# schematic.net
KiCad netlist of a schematic drawn in Altium Designer
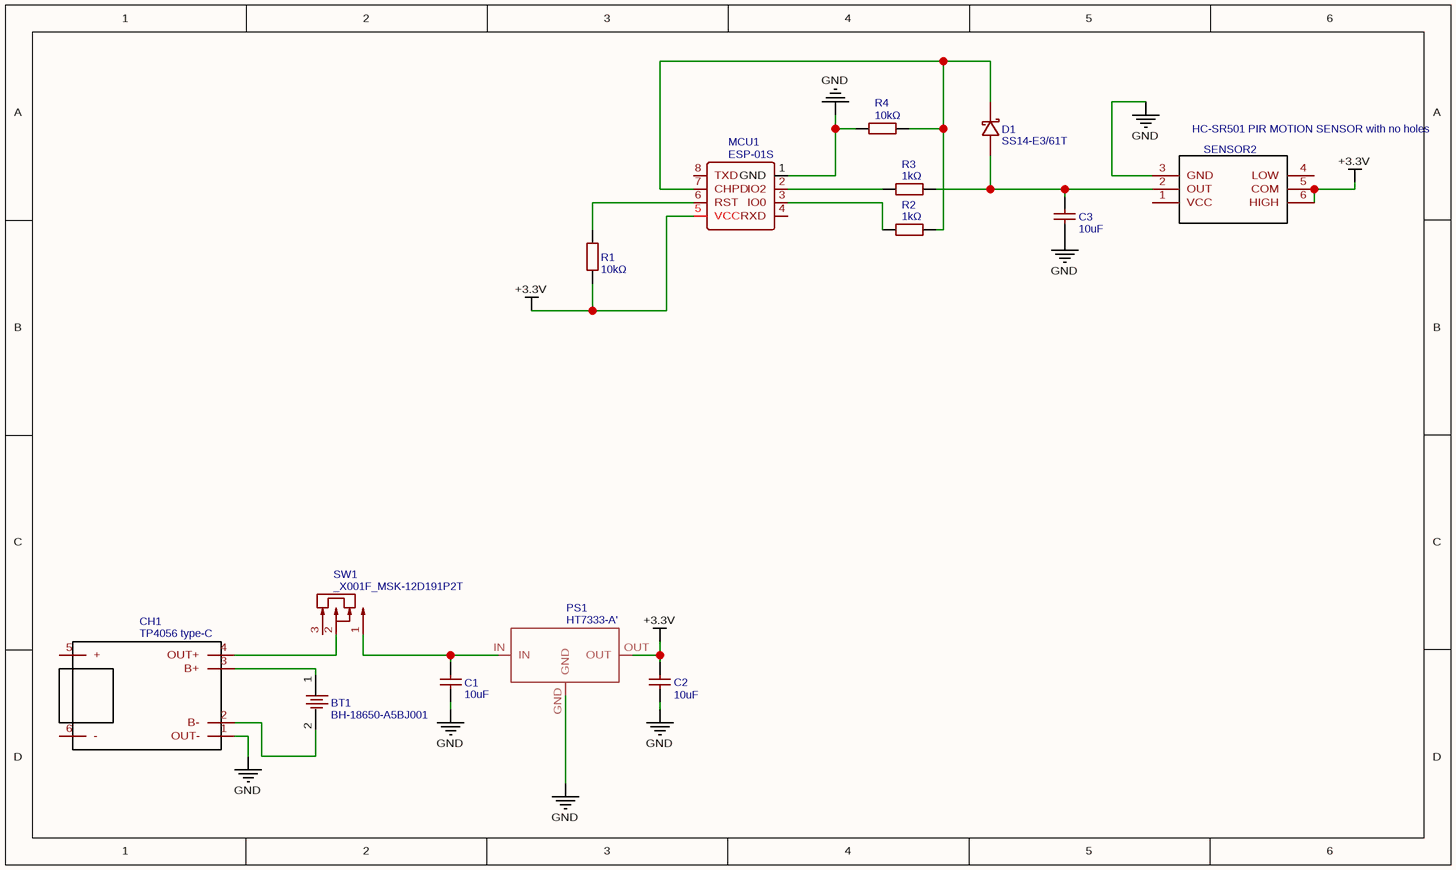
[diagram p0: schematic.schdoc]

(export (version "E")
  (design (tool "Eeschema 10.0.6"))
  (components
    (comp (ref "BT1")
      (value "BH-18650-A5BJ001")
      (fields (field (name "MANUFACTURER") "MYOUNG(美阳)") (field (name "CONTRIBUTOR") "lcsc"))
      (libsource (lib "altium-import") (part "root_3_BH-18650-A5BJ001_"))
    )
    (comp (ref "C1")
      (value "10uF")
      (fields
        (field (name "MANUFACTURER PART") "CL21A106KOQNNNE")
        (field (name "MANUFACTURER") "SAMSUNG(三星)")
      )
      (libsource (lib "altium-import") (part "root_1_10uF_"))
    )
    (comp (ref "C2")
      (value "10uF")
      (fields
        (field (name "MANUFACTURER PART") "CL21A106KOQNNNE")
        (field (name "MANUFACTURER") "SAMSUNG(三星)")
      )
      (libsource (lib "altium-import") (part "root_3_10uF_"))
    )
    (comp (ref "C3")
      (value "10uF")
      (fields
        (field (name "MANUFACTURER PART") "CL21A106KOQNNNE")
        (field (name "MANUFACTURER") "SAMSUNG(三星)")
      )
      (libsource (lib "altium-import") (part "root_3_10uF_"))
    )
    (comp (ref "CH1")
      (value "TP4056 type-C")
      (fields (field (name "CONTRIBUTOR") "red2211"))
      (libsource (lib "altium-import") (part "root_1_TP4056 type-C_"))
    )
    (comp (ref "D1")
      (value "SS14-E3/61T")
      (fields (field (name "MANUFACTURER") "VISHAY(威世)"))
      (libsource (lib "altium-import") (part "root_3_SS14-E3/61T_"))
    )
    (comp (ref "MCU1")
      (value "ESP-01S")
      (fields (field (name "MANUFACTURER") "Ai-Thinker"))
      (libsource (lib "altium-import") (part "root_3_ESP-01S_"))
    )
    (comp (ref "PS1")
      (value "HT7333-A'")
      (fields (field (name "CONTRIBUTOR") "userweb"))
      (libsource (lib "altium-import") (part "root_0_HT7333-A'_"))
    )
    (comp (ref "R1")
      (value "10kΩ")
      (fields
        (field (name "MANUFACTURER") "UNI-ROYAL(厚声)")
        (field (name "MANUFACTURER PART") "1206W4F1002T5E")
      )
      (libsource (lib "altium-import") (part "root_1_10kΩ_"))
    )
    (comp (ref "R2")
      (value "1kΩ")
      (fields
        (field (name "MANUFACTURER") "UNI-ROYAL(厚声)")
        (field (name "MANUFACTURER PART") "1206W4F1001T5E")
      )
      (libsource (lib "altium-import") (part "root_0_1kΩ_"))
    )
    (comp (ref "R3")
      (value "1kΩ")
      (fields
        (field (name "MANUFACTURER") "UNI-ROYAL(厚声)")
        (field (name "MANUFACTURER PART") "1206W4F1001T5E")
      )
      (libsource (lib "altium-import") (part "root_0_1kΩ_"))
    )
    (comp (ref "R4")
      (value "10kΩ")
      (fields
        (field (name "MANUFACTURER") "UNI-ROYAL(厚声)")
        (field (name "MANUFACTURER PART") "1206W4F1002T5E")
      )
      (libsource (lib "altium-import") (part "root_2_10kΩ_"))
    )
    (comp (ref "SENSOR2")
      (value "HC-SR501 PIR MOTION SENSOR with no holes")
      (fields (field (name "CONTRIBUTOR") "aryadpram"))
      (libsource (lib "altium-import") (part "root_0_HC-SR501 PIR MOTION SENSOR with no holes_"))
    )
    (comp (ref "SW1")
      (value "_X001F_MSK-12D191P2T")
      (fields (field (name "MANUFACTURER PART") "_x001F_MSK-12D191P2T") (field (name "CONTRIBUTOR") "lcsc"))
      (libsource (lib "altium-import") (part "root_2__X001F_MSK-12D191P2T_"))
    )
  )
  (nets
    (net (code "1") (name "+3.3V") (class "Default")
      (node (ref "C2") (pin "1") (pinfunction "1_1") (pintype "passive"))
      (node (ref "MCU1") (pin "5") (pinfunction "VCC_5") (pintype "passive"))
      (node (ref "PS1") (pin "OUT") (pinfunction "OUT_OUT") (pintype "passive"))
      (node (ref "R1") (pin "1") (pinfunction "1_1") (pintype "passive"))
      (node (ref "SENSOR2") (pin "5") (pinfunction "COM_5") (pintype "passive"))
      (node (ref "SENSOR2") (pin "6") (pinfunction "HIGH_6") (pintype "passive"))
    )
    (net (code "2") (name "GND") (class "Default")
      (node (ref "C1") (pin "1") (pinfunction "1_1") (pintype "passive"))
      (node (ref "C2") (pin "2") (pinfunction "2_2") (pintype "passive"))
      (node (ref "C3") (pin "2") (pinfunction "2_2") (pintype "passive"))
      (node (ref "CH1") (pin "1") (pinfunction "OUT-_1") (pintype "passive"))
      (node (ref "MCU1") (pin "1") (pinfunction "GND_1") (pintype "passive"))
      (node (ref "PS1") (pin "GND") (pinfunction "GND_GND") (pintype "passive"))
      (node (ref "R4") (pin "2") (pinfunction "2_2") (pintype "passive"))
      (node (ref "SENSOR2") (pin "3") (pinfunction "GND_3") (pintype "passive"))
    )
    (net (code "3") (name "Net-(C1-Pad2)") (class "Default")
      (node (ref "C1") (pin "2") (pinfunction "2_2") (pintype "passive"))
      (node (ref "PS1") (pin "IN") (pinfunction "IN_IN") (pintype "passive"))
      (node (ref "SW1") (pin "1") (pinfunction "1_1") (pintype "passive"))
    )
    (net (code "4") (name "Net-(CH1-B+)") (class "Default")
      (node (ref "BT1") (pin "1") (pinfunction "1_1") (pintype "passive"))
      (node (ref "CH1") (pin "3") (pinfunction "B+_3") (pintype "passive"))
    )
    (net (code "5") (name "Net-(CH1-B-)") (class "Default")
      (node (ref "BT1") (pin "2") (pinfunction "2_2") (pintype "passive"))
      (node (ref "CH1") (pin "2") (pinfunction "B-_2") (pintype "passive"))
    )
    (net (code "6") (name "Net-(CH1-OUT+)") (class "Default")
      (node (ref "CH1") (pin "4") (pinfunction "OUT+_4") (pintype "passive"))
      (node (ref "SW1") (pin "2") (pinfunction "2_2") (pintype "passive"))
    )
    (net (code "7") (name "Net-(D1-A)") (class "Default")
      (node (ref "C3") (pin "1") (pinfunction "1_1") (pintype "passive"))
      (node (ref "D1") (pin "2") (pinfunction "A_2") (pintype "passive"))
      (node (ref "R3") (pin "2") (pinfunction "2_2") (pintype "passive"))
      (node (ref "SENSOR2") (pin "2") (pinfunction "OUT_2") (pintype "passive"))
    )
    (net (code "8") (name "Net-(D1-K)") (class "Default")
      (node (ref "D1") (pin "1") (pinfunction "K_1") (pintype "passive"))
      (node (ref "MCU1") (pin "7") (pinfunction "CHPD_7") (pintype "passive"))
      (node (ref "R2") (pin "2") (pinfunction "2_2") (pintype "passive"))
      (node (ref "R4") (pin "1") (pinfunction "1_1") (pintype "passive"))
    )
    (net (code "9") (name "Net-(MCU1-IO0)") (class "Default")
      (node (ref "MCU1") (pin "3") (pinfunction "IO0_3") (pintype "passive"))
      (node (ref "R2") (pin "1") (pinfunction "1_1") (pintype "passive"))
    )
    (net (code "10") (name "Net-(MCU1-IO2)") (class "Default")
      (node (ref "MCU1") (pin "2") (pinfunction "IO2_2") (pintype "passive"))
      (node (ref "R3") (pin "1") (pinfunction "1_1") (pintype "passive"))
    )
    (net (code "11") (name "Net-(MCU1-RST)") (class "Default")
      (node (ref "MCU1") (pin "6") (pinfunction "RST_6") (pintype "passive"))
      (node (ref "R1") (pin "2") (pinfunction "2_2") (pintype "passive"))
    )
    (net (code "12") (name "unconnected-(CH1-+-Pad5)") (class "Default")
      (node (ref "CH1") (pin "5") (pinfunction "+_5") (pintype "passive"))
    )
    (net (code "13") (name "unconnected-(CH1---Pad6)") (class "Default")
      (node (ref "CH1") (pin "6") (pinfunction "-_6") (pintype "passive"))
    )
    (net (code "14") (name "unconnected-(MCU1-RXD-Pad4)") (class "Default")
      (node (ref "MCU1") (pin "4") (pinfunction "RXD_4") (pintype "passive"))
    )
    (net (code "15") (name "unconnected-(MCU1-TXD-Pad8)") (class "Default")
      (node (ref "MCU1") (pin "8") (pinfunction "TXD_8") (pintype "passive"))
    )
    (net (code "16") (name "unconnected-(SENSOR2-LOW-Pad4)") (class "Default")
      (node (ref "SENSOR2") (pin "4") (pinfunction "LOW_4") (pintype "passive"))
    )
    (net (code "17") (name "unconnected-(SENSOR2-VCC-Pad1)") (class "Default")
      (node (ref "SENSOR2") (pin "1") (pinfunction "VCC_1") (pintype "passive"))
    )
    (net (code "18") (name "unconnected-(SW1-Pad3)") (class "Default")
      (node (ref "SW1") (pin "3") (pinfunction "3_3") (pintype "passive"))
    )
  )
)
